# USB.net
KiCad netlist of a schematic drawn in EasyEDA Pro
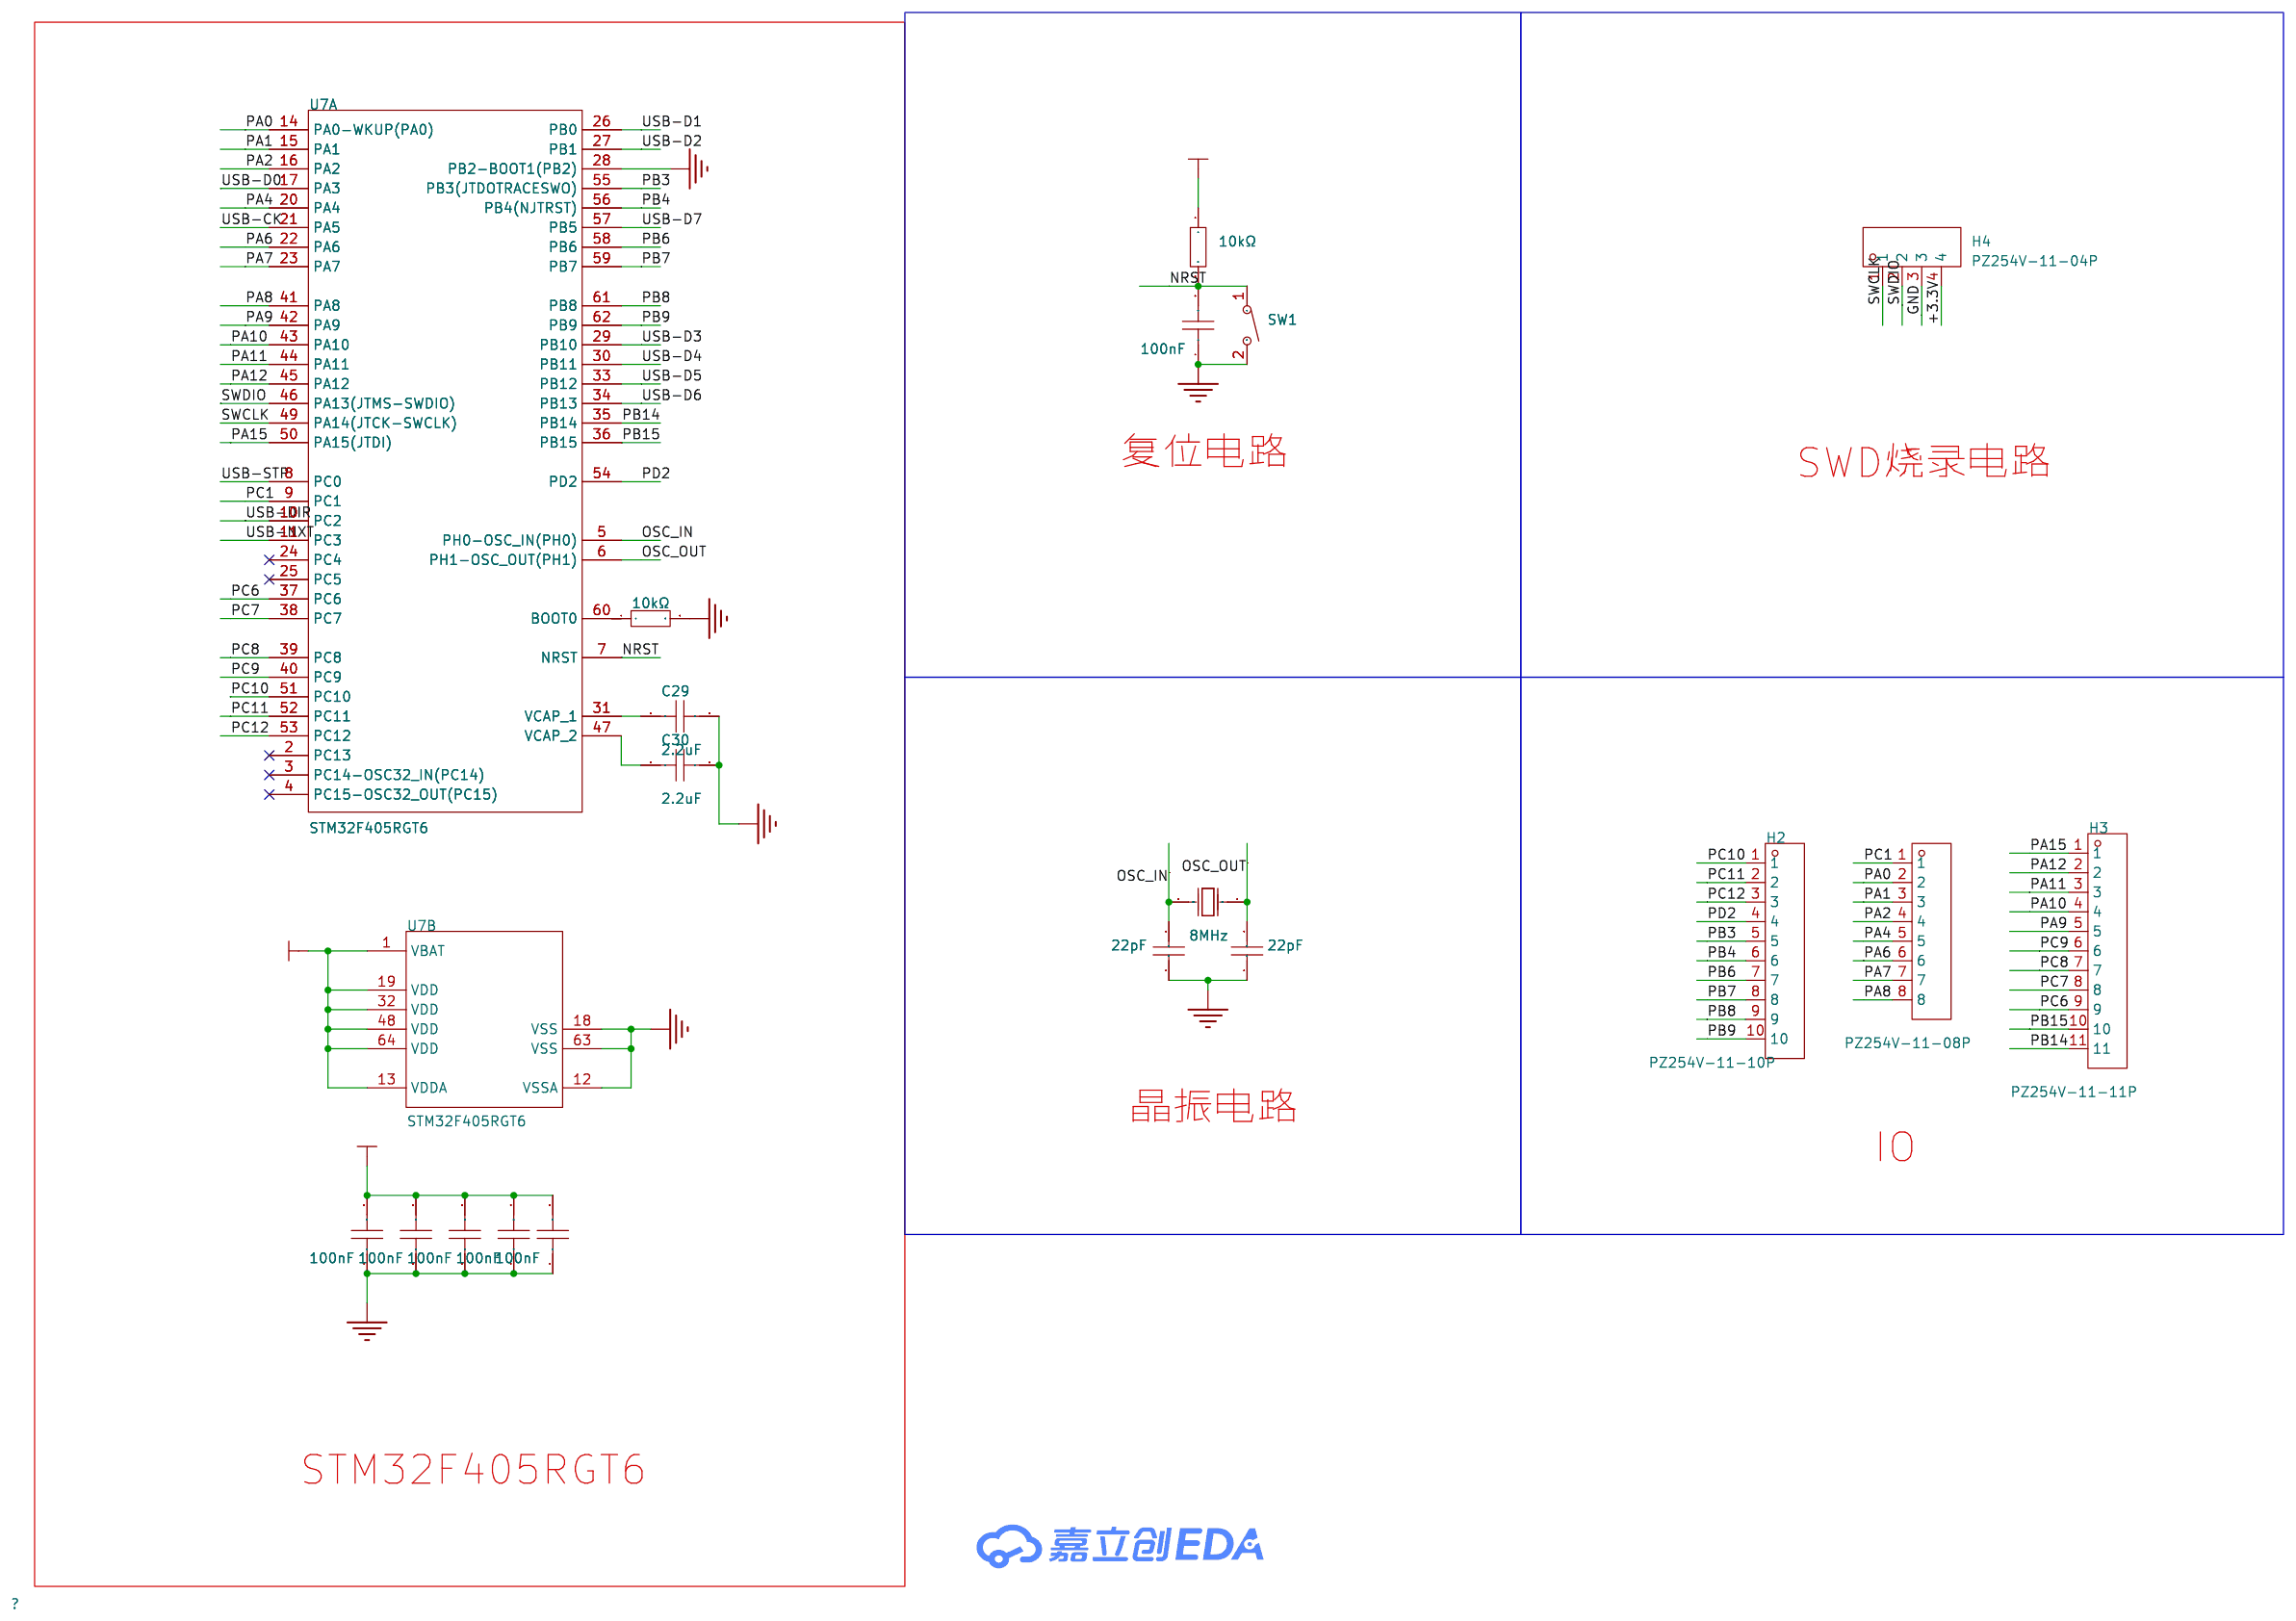
[diagram p0: P1]
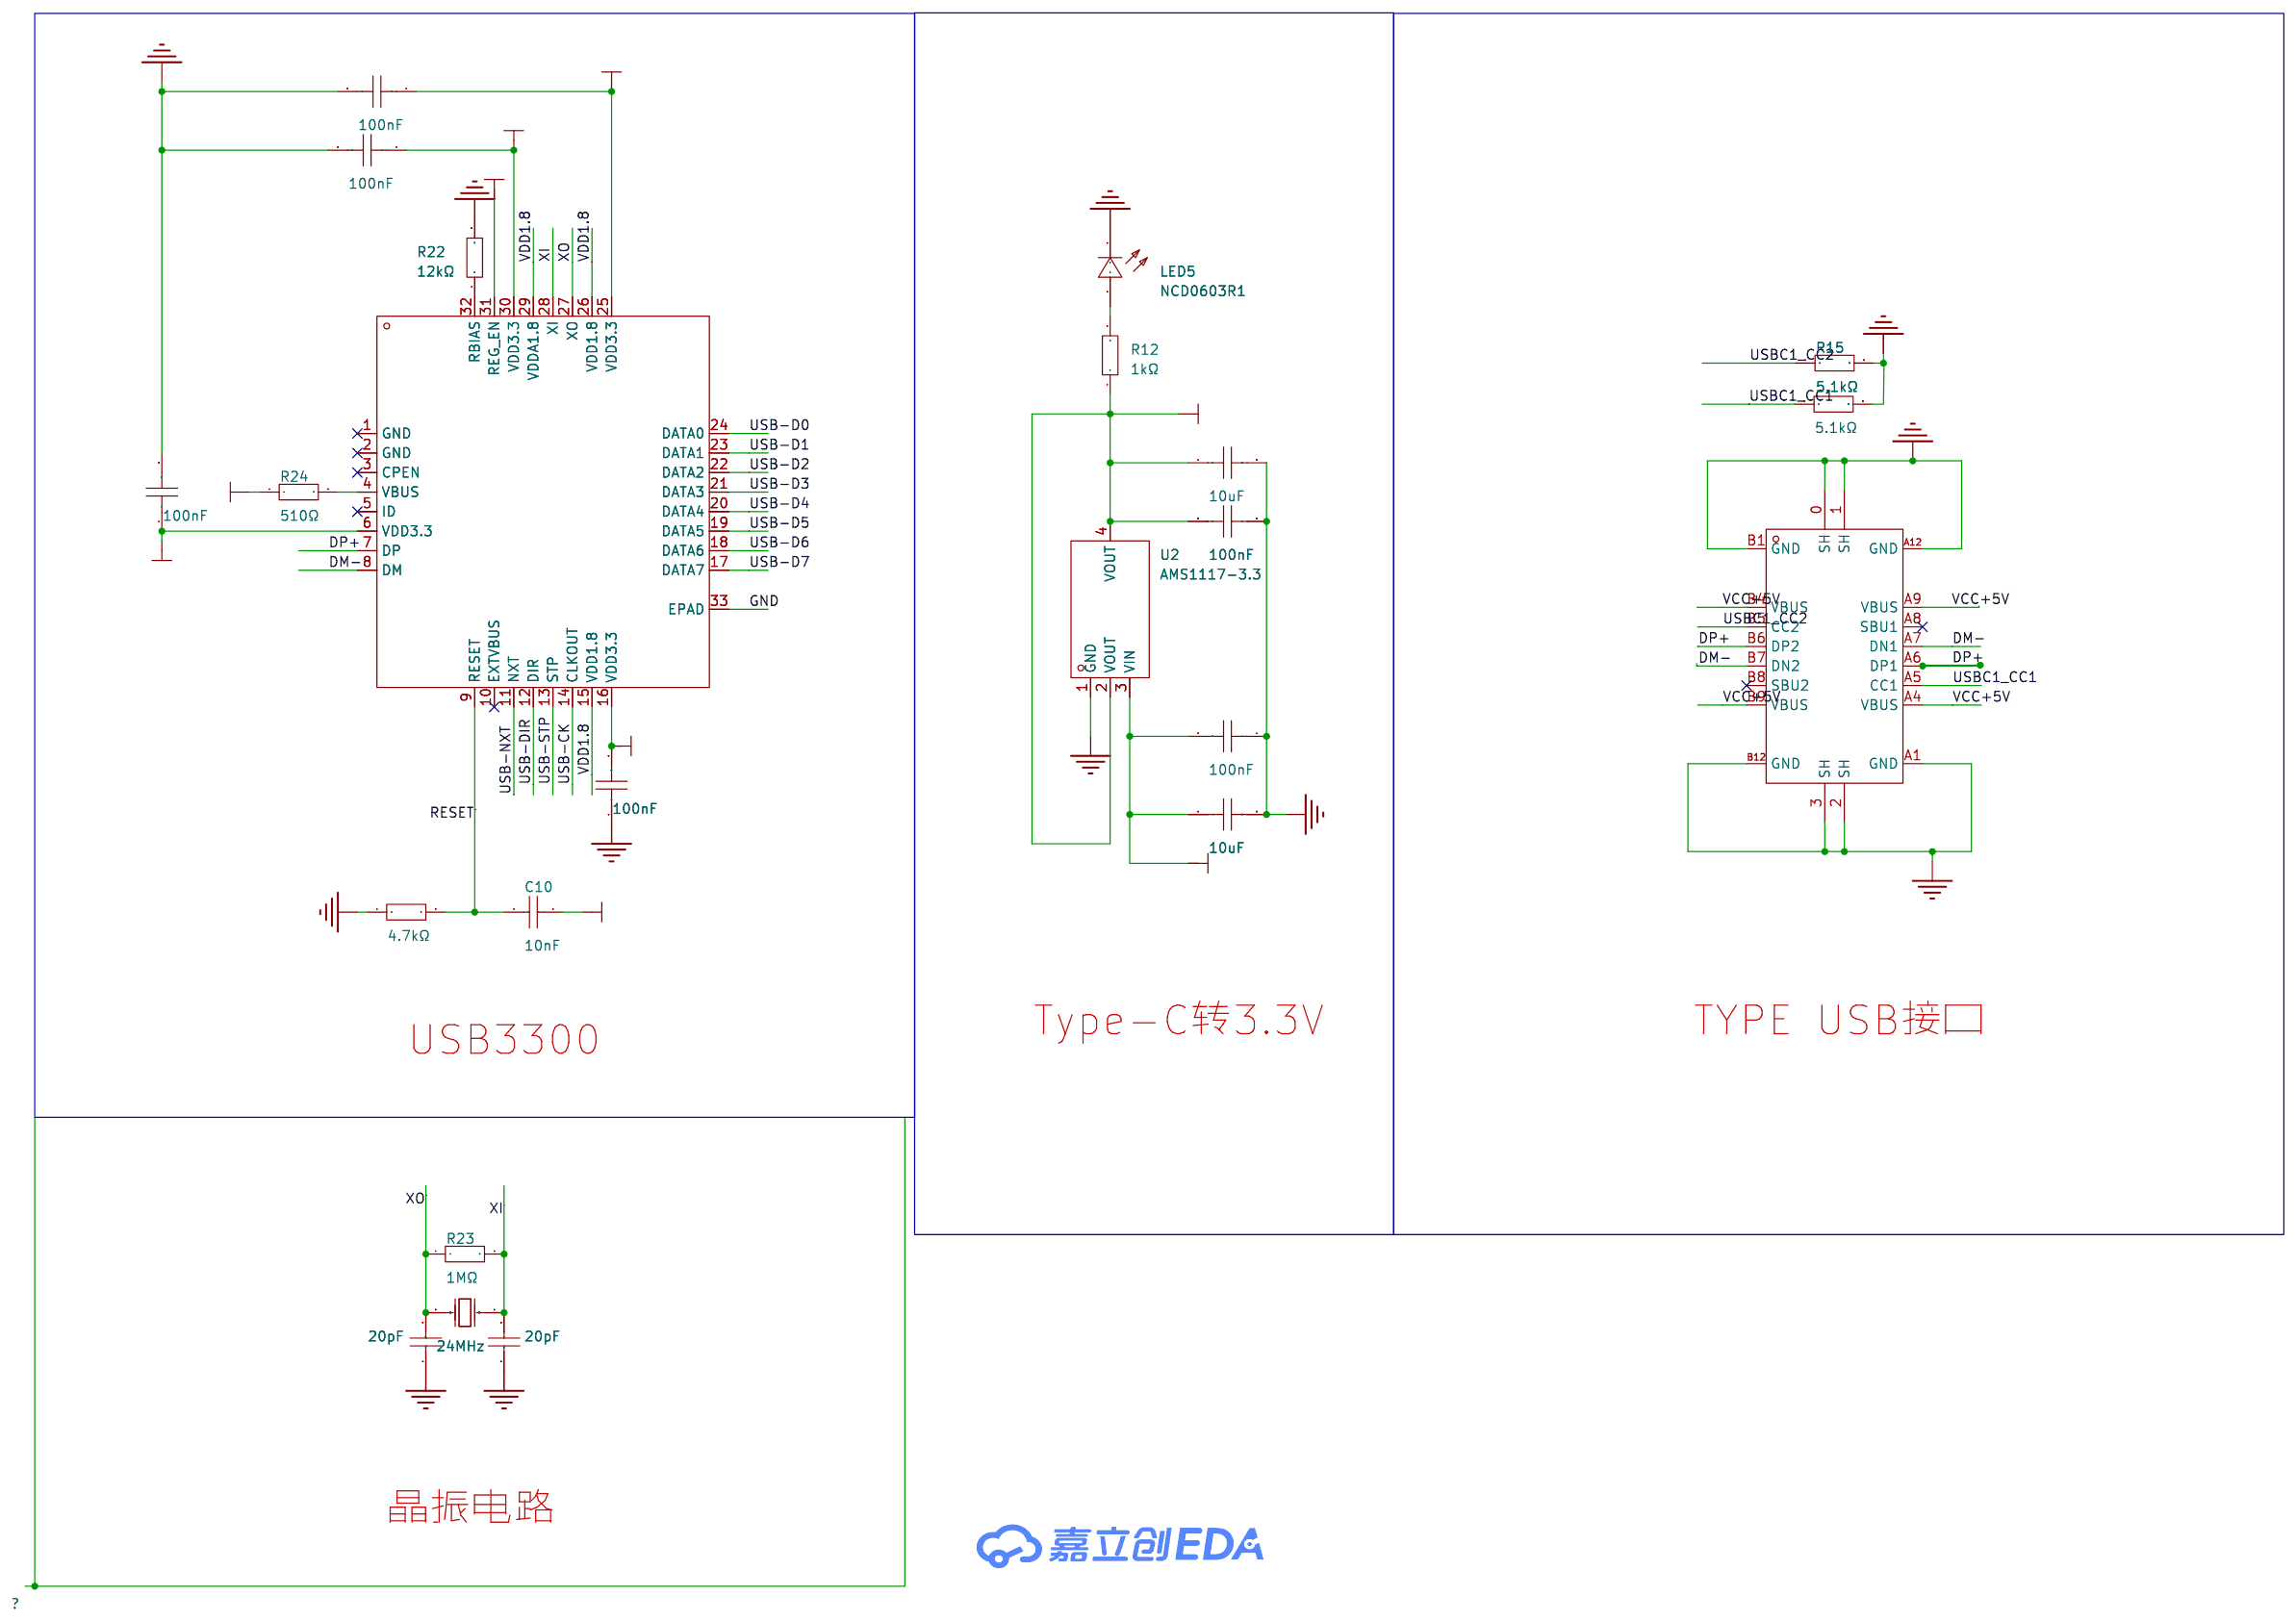
[diagram p1: P2]

(export (version "E")
  (design (tool "Eeschema 10.0.6"))
  (components
    (comp (ref "C20")
      (value "22pF")
      (footprint "easyedapro:C0603")
      (description "容值:22pF;精度:±5%;额定电压:50V;材质(温度系数):C0G;")
      (fields
        (field (name "Manufacturer Part") "CL10C220JB8NNNC")
        (field (name "Manufacturer") "SAMSUNG(三星)")
      )
      (libsource (lib "easyedapro") (part "CL10C220JB8NNNC"))
    )
    (comp (ref "C21")
      (value "22pF")
      (footprint "easyedapro:C0603")
      (description "容值:22pF;精度:±5%;额定电压:50V;材质(温度系数):C0G;")
      (fields
        (field (name "Manufacturer Part") "CL10C220JB8NNNC")
        (field (name "Manufacturer") "SAMSUNG(三星)")
      )
      (libsource (lib "easyedapro") (part "CL10C220JB8NNNC"))
    )
    (comp (ref "C22")
      (value "100nF")
      (footprint "easyedapro:C0603")
      (description "容值:100nF;精度:±10%;额定电压:50V;材质(温度系数):X7R;")
      (fields
        (field (name "Manufacturer Part") "CGA0603X7R104K500JT")
        (field (name "Manufacturer") "HRE(芯声)")
      )
      (libsource (lib "easyedapro") (part "CGA0603X7R104K500JT"))
    )
    (comp (ref "C29")
      (value "2.2uF")
      (footprint "easyedapro:C0603")
      (description "容值:2.2uF;精度:±10%;额定电压:50V;材质(温度系数):X5R;")
      (fields
        (field (name "Manufacturer Part") "CL10A225KB8NNNC")
        (field (name "Manufacturer") "SAMSUNG(三星)")
      )
      (libsource (lib "easyedapro") (part "CL10A225KB8NNNC"))
    )
    (comp (ref "C30")
      (value "2.2uF")
      (footprint "easyedapro:C0603")
      (description "容值:2.2uF;精度:±10%;额定电压:50V;材质(温度系数):X5R;")
      (fields
        (field (name "Manufacturer Part") "CL10A225KB8NNNC")
        (field (name "Manufacturer") "SAMSUNG(三星)")
      )
      (libsource (lib "easyedapro") (part "CL10A225KB8NNNC"))
    )
    (comp (ref "C35")
      (value "100nF")
      (footprint "easyedapro:C0603")
      (description "容值:100nF;精度:±10%;额定电压:50V;材质(温度系数):X7R;")
      (fields
        (field (name "Manufacturer Part") "CGA0603X7R104K500JT")
        (field (name "Manufacturer") "HRE(芯声)")
      )
      (libsource (lib "easyedapro") (part "CGA0603X7R104K500JT"))
    )
    (comp (ref "C36")
      (value "100nF")
      (footprint "easyedapro:C0603")
      (description "容值:100nF;精度:±10%;额定电压:50V;材质(温度系数):X7R;")
      (fields
        (field (name "Manufacturer Part") "CGA0603X7R104K500JT")
        (field (name "Manufacturer") "HRE(芯声)")
      )
      (libsource (lib "easyedapro") (part "CGA0603X7R104K500JT"))
    )
    (comp (ref "C37")
      (value "100nF")
      (footprint "easyedapro:C0603")
      (description "容值:100nF;精度:±10%;额定电压:50V;材质(温度系数):X7R;")
      (fields
        (field (name "Manufacturer Part") "CGA0603X7R104K500JT")
        (field (name "Manufacturer") "HRE(芯声)")
      )
      (libsource (lib "easyedapro") (part "CGA0603X7R104K500JT"))
    )
    (comp (ref "C38")
      (value "100nF")
      (footprint "easyedapro:C0603")
      (description "容值:100nF;精度:±10%;额定电压:50V;材质(温度系数):X7R;")
      (fields
        (field (name "Manufacturer Part") "CGA0603X7R104K500JT")
        (field (name "Manufacturer") "HRE(芯声)")
      )
      (libsource (lib "easyedapro") (part "CGA0603X7R104K500JT"))
    )
    (comp (ref "C39")
      (value "100nF")
      (footprint "easyedapro:C0603")
      (description "容值:100nF;精度:±10%;额定电压:50V;材质(温度系数):X7R;")
      (fields
        (field (name "Manufacturer Part") "CGA0603X7R104K500JT")
        (field (name "Manufacturer") "HRE(芯声)")
      )
      (libsource (lib "easyedapro") (part "CGA0603X7R104K500JT"))
    )
    (comp (ref "H1")
      (value "PZ254V-11-08P")
      (footprint "easyedapro:HDR-TH_8P-P2.54-V-M")
      (fields (field (name "Manufacturer") "XFCN(兴飞)"))
      (libsource (lib "easyedapro") (part "PZ254V-11-08P"))
    )
    (comp (ref "H2")
      (value "PZ254V-11-10P")
      (footprint "easyedapro:HDR-TH_10P-P2.54-V-M")
      (fields (field (name "Manufacturer") "XFCN(兴飞)"))
      (libsource (lib "easyedapro") (part "PZ254V-11-10P"))
    )
    (comp (ref "H3")
      (value "PZ254V-11-11P")
      (footprint "easyedapro:HDR-TH_11P-P2.54-V-M")
      (fields (field (name "Manufacturer") "XFCN(兴飞)"))
      (libsource (lib "easyedapro") (part "PZ254V-11-11P"))
    )
    (comp (ref "H4")
      (value "PZ254V-11-04P")
      (footprint "easyedapro:HDR-TH_4P-P2.54-V-M")
      (fields (field (name "Manufacturer") "XFCN(兴飞)"))
      (libsource (lib "easyedapro") (part "PZ254V-11-04P_C2691448"))
    )
    (comp (ref "R18")
      (value "10kΩ")
      (footprint "easyedapro:R0603")
      (description "电阻类型:厚膜电阻;阻值:10kΩ;精度:±1%;功率:100mW;最大工作电压:75V;温度系数:±100ppm/°C;")
      (fields
        (field (name "Manufacturer Part") "0603WAF1002T5E")
        (field (name "Manufacturer") "UNI-ROYAL(厚声)")
      )
      (libsource (lib "easyedapro") (part "0603WAF1002T5E"))
    )
    (comp (ref "R19")
      (value "10kΩ")
      (footprint "easyedapro:R0603")
      (description "电阻类型:厚膜电阻;阻值:10kΩ;精度:±1%;功率:100mW;最大工作电压:75V;温度系数:±100ppm/°C;")
      (fields
        (field (name "Manufacturer Part") "0603WAF1002T5E")
        (field (name "Manufacturer") "UNI-ROYAL(厚声)")
      )
      (libsource (lib "easyedapro") (part "0603WAF1002T5E"))
    )
    (comp (ref "SW1")
      (value "TS-1092S-B3D2-G")
      (footprint "easyedapro:SW-SMD_L6.1-W3.6-LS7.9")
      (description "电路结构:单刀单掷;按钮形状:矩形按钮;作用力:250gf;安装方式:立贴;开关长度:6.1mm;开关宽度:3.6mm;开关高度:2.5mm;带支架:不带;机械寿命:-;")
      (fields (field (name "Manufacturer") "Yuandi(元迪)"))
      (libsource (lib "easyedapro") (part "TS-1092S-B3D2-G"))
    )
    (comp (ref "U7")
      (value "STM32F405RGT6")
      (footprint "easyedapro:LQFP-64_L10.0-W10.0-P0.50-LS12.0-BL")
      (description "CPU内核:ARM-M4;CPU最大主频:168MHz;应用领域:-;")
      (fields (field (name "Manufacturer") "ST(意法半导体)"))
      (libsource (lib "easyedapro") (part "STM32F405RGT6"))
    )
    (comp (ref "X3")
      (value "8MHz")
      (footprint "easyedapro:OSC-SMD_L5.0-W3.2")
      (description "晶振类型:贴片晶振;频率:8MHz;常温频差:±30ppm;外接负载电容:20pF;频率稳定度(全温):±20ppm;")
      (fields (field (name "Manufacturer Part") "TAXM8M2QLFCDT1T") (field (name "Manufacturer") "YJX(雅晶鑫)"))
      (libsource (lib "easyedapro") (part "SMD-5032_2P 8M 20pf 30ppm"))
    )
    (comp (ref "C10")
      (value "10nF")
      (footprint "easyedapro:C0603")
      (description "容值:10nF;精度:±10%;额定电压:50V;材质(温度系数):X7R;")
      (fields
        (field (name "Manufacturer Part") "CC0603KRX7R9BB103")
        (field (name "Manufacturer") "YAGEO(国巨)")
      )
      (libsource (lib "easyedapro") (part "CC0603KRX7R9BB103"))
    )
    (comp (ref "C11")
      (value "10uF")
      (footprint "easyedapro:C0603")
      (description "容值:10uF;精度:±10%;额定电压:10V;材质(温度系数):X5R;")
      (fields
        (field (name "Manufacturer Part") "CGA0603X5R106K100JT")
        (field (name "Manufacturer") "HRE(芯声)")
      )
      (libsource (lib "easyedapro") (part "CGA0603X5R106K100JT"))
    )
    (comp (ref "C12")
      (value "100nF")
      (footprint "easyedapro:C0603")
      (description "容值:100nF;精度:±10%;额定电压:50V;材质(温度系数):X7R;")
      (fields
        (field (name "Manufacturer Part") "CGA0603X7R104K500JT")
        (field (name "Manufacturer") "HRE(芯声)")
      )
      (libsource (lib "easyedapro") (part "CGA0603X7R104K500JT"))
    )
    (comp (ref "C13")
      (value "100nF")
      (footprint "easyedapro:C0603")
      (description "容值:100nF;精度:±10%;额定电压:50V;材质(温度系数):X7R;")
      (fields
        (field (name "Manufacturer Part") "CGA0603X7R104K500JT")
        (field (name "Manufacturer") "HRE(芯声)")
      )
      (libsource (lib "easyedapro") (part "CGA0603X7R104K500JT"))
    )
    (comp (ref "C14")
      (value "10uF")
      (footprint "easyedapro:C0603")
      (description "容值:10uF;精度:±10%;额定电压:10V;材质(温度系数):X5R;")
      (fields
        (field (name "Manufacturer Part") "CGA0603X5R106K100JT")
        (field (name "Manufacturer") "HRE(芯声)")
      )
      (libsource (lib "easyedapro") (part "CGA0603X5R106K100JT"))
    )
    (comp (ref "C23")
      (value "20pF")
      (footprint "easyedapro:C0603")
      (description "容值:20pF;精度:±5%;额定电压:50V;材质(温度系数):C0G;")
      (fields
        (field (name "Manufacturer Part") "CL10C200JB8NNNC")
        (field (name "Manufacturer") "SAMSUNG(三星)")
      )
      (libsource (lib "easyedapro") (part "CL10C200JB8NNNC"))
    )
    (comp (ref "C24")
      (value "20pF")
      (footprint "easyedapro:C0603")
      (description "容值:20pF;精度:±5%;额定电压:50V;材质(温度系数):C0G;")
      (fields
        (field (name "Manufacturer Part") "CL10C200JB8NNNC")
        (field (name "Manufacturer") "SAMSUNG(三星)")
      )
      (libsource (lib "easyedapro") (part "CL10C200JB8NNNC"))
    )
    (comp (ref "C31")
      (value "100nF")
      (footprint "easyedapro:C0603")
      (description "容值:100nF;精度:±10%;额定电压:50V;材质(温度系数):X7R;")
      (fields
        (field (name "Manufacturer Part") "CGA0603X7R104K500JT")
        (field (name "Manufacturer") "HRE(芯声)")
      )
      (libsource (lib "easyedapro") (part "CGA0603X7R104K500JT"))
    )
    (comp (ref "C32")
      (value "100nF")
      (footprint "easyedapro:C0603")
      (description "容值:100nF;精度:±10%;额定电压:50V;材质(温度系数):X7R;")
      (fields
        (field (name "Manufacturer Part") "CGA0603X7R104K500JT")
        (field (name "Manufacturer") "HRE(芯声)")
      )
      (libsource (lib "easyedapro") (part "CGA0603X7R104K500JT"))
    )
    (comp (ref "C33")
      (value "100nF")
      (footprint "easyedapro:C0603")
      (description "容值:100nF;精度:±10%;额定电压:50V;材质(温度系数):X7R;")
      (fields
        (field (name "Manufacturer Part") "CGA0603X7R104K500JT")
        (field (name "Manufacturer") "HRE(芯声)")
      )
      (libsource (lib "easyedapro") (part "CGA0603X7R104K500JT"))
    )
    (comp (ref "C34")
      (value "100nF")
      (footprint "easyedapro:C0603")
      (description "容值:100nF;精度:±10%;额定电压:50V;材质(温度系数):X7R;")
      (fields
        (field (name "Manufacturer Part") "CGA0603X7R104K500JT")
        (field (name "Manufacturer") "HRE(芯声)")
      )
      (libsource (lib "easyedapro") (part "CGA0603X7R104K500JT"))
    )
    (comp (ref "LED5")
      (value "NCD0603R1")
      (footprint "easyedapro:LED0603-RD_RED")
      (fields (field (name "Manufacturer") "国星光电"))
      (libsource (lib "easyedapro") (part "FC-DA1608HRK-620D"))
    )
    (comp (ref "R11")
      (value "4.7kΩ")
      (footprint "easyedapro:R0603")
      (description "电阻类型:厚膜电阻;阻值:4.7kΩ;精度:±1%;功率:100mW;最大工作电压:75V;温度系数:±100ppm/°C;")
      (fields
        (field (name "Manufacturer Part") "0603WAF4701T5E")
        (field (name "Manufacturer") "UNI-ROYAL(厚声)")
      )
      (libsource (lib "easyedapro") (part "0603WAF4701T5E"))
    )
    (comp (ref "R12")
      (value "1kΩ")
      (footprint "easyedapro:R0603")
      (description "电阻类型:厚膜电阻;阻值:1kΩ;精度:±1%;功率:100mW;最大工作电压:75V;温度系数:±100ppm/°C;")
      (fields
        (field (name "Manufacturer Part") "0603WAF1001T5E")
        (field (name "Manufacturer") "UNI-ROYAL(厚声)")
      )
      (libsource (lib "easyedapro") (part "0603WAF1001T5E"))
    )
    (comp (ref "R14")
      (value "5.1kΩ")
      (footprint "easyedapro:R0603")
      (description "电阻类型:厚膜电阻;阻值:5.1kΩ;精度:±1%;功率:100mW;最大工作电压:75V;温度系数:±100ppm/°C;")
      (fields
        (field (name "Manufacturer Part") "0603WAF5101T5E")
        (field (name "Manufacturer") "UNI-ROYAL(厚声)")
      )
      (libsource (lib "easyedapro") (part "0603WAF5101T5E"))
    )
    (comp (ref "R15")
      (value "5.1kΩ")
      (footprint "easyedapro:R0603")
      (description "电阻类型:厚膜电阻;阻值:5.1kΩ;精度:±1%;功率:100mW;最大工作电压:75V;温度系数:±100ppm/°C;")
      (fields
        (field (name "Manufacturer Part") "0603WAF5101T5E")
        (field (name "Manufacturer") "UNI-ROYAL(厚声)")
      )
      (libsource (lib "easyedapro") (part "0603WAF5101T5E"))
    )
    (comp (ref "R22")
      (value "12kΩ")
      (footprint "easyedapro:R0603")
      (description "电阻类型:厚膜电阻;阻值:12kΩ;精度:±1%;功率:100mW;最大工作电压:75V;温度系数:±100ppm/°C;")
      (fields
        (field (name "Manufacturer Part") "0603WAF1202T5E")
        (field (name "Manufacturer") "UNI-ROYAL(厚声)")
      )
      (libsource (lib "easyedapro") (part "0603WAF1202T5E"))
    )
    (comp (ref "R23")
      (value "1MΩ")
      (footprint "easyedapro:R0603")
      (description "电阻类型:厚膜电阻;阻值:1MΩ;精度:±1%;功率:100mW;最大工作电压:75V;温度系数:±100ppm/°C;")
      (fields
        (field (name "Manufacturer Part") "0603WAF1004T5E")
        (field (name "Manufacturer") "UNI-ROYAL(厚声)")
      )
      (libsource (lib "easyedapro") (part "0603WAF1004T5E"))
    )
    (comp (ref "R24")
      (value "510Ω")
      (footprint "easyedapro:R0603")
      (description "电阻类型:厚膜电阻;阻值:510Ω;精度:±1%;功率:100mW;最大工作电压:75V;温度系数:±100ppm/°C;")
      (fields
        (field (name "Manufacturer Part") "0603WAF5100T5E")
        (field (name "Manufacturer") "UNI-ROYAL(厚声)")
      )
      (libsource (lib "easyedapro") (part "0603WAF5100T5E"))
    )
    (comp (ref "U2")
      (value "AMS1117-3.3")
      (footprint "easyedapro:SOT-223-3_L6.5-W3.4-P2.30-LS7.0-BR")
      (description "输出类型:固定;最大输入电压:-;输出电压:3.3V;最大输出电流:1A;电源纹波抑制比(PSRR):72dB@(120Hz);输出极性:正极;")
      (fields (field (name "Manufacturer") "AMS"))
      (libsource (lib "easyedapro") (part "AMS1117-3.3"))
    )
    (comp (ref "USB3301")
      (value "USB3300-EZK-TR")
      (footprint "easyedapro:QFN-32_L5.0-W5.0-P0.50-BL-EP3.4")
      (description "应用功能:控制器;接口协议:-;")
      (fields (field (name "Manufacturer") "MICROCHIP(美国微芯)"))
      (libsource (lib "easyedapro") (part "USB3300-EZK-TR"))
    )
    (comp (ref "USBC2")
      (value "TYPE-C-31-M-12")
      (footprint "easyedapro:USB-C_SMD-TYPE-C-31-M-12")
      (description "连接器类型:Type-C;标准:-;公母:母;安装方式:-;触点数量:16P;端口数量:1;额定电流 - 电源:5A;工作温度范围:-;")
      (fields (field (name "Manufacturer") "韩国韩荣"))
      (libsource (lib "easyedapro") (part "TYPE-C-31-M-12"))
    )
    (comp (ref "X4")
      (value "24MHz")
      (footprint "easyedapro:HC-49US_L11.5-W4.5-P4.88")
      (description "晶振类型:直插晶振;频率:24MHz;常温频差:±20ppm;外接负载电容:20pF;频率稳定度(全温):±30ppm;")
      (fields (field (name "Manufacturer Part") "X49SD24MSD2SC") (field (name "Manufacturer") "YXC(扬兴晶振)"))
      (libsource (lib "easyedapro") (part "X49SD24MSD2SC"))
    )
  )
  (nets
    (net (code "1") (name "+3.3V") (class "Default")
      (node (ref "C10") (pin "2") (pinfunction "2_2") (pintype "input"))
      (node (ref "C13") (pin "2") (pinfunction "2_2") (pintype "unspecified"))
      (node (ref "C14") (pin "1") (pinfunction "1_1") (pintype "unspecified"))
      (node (ref "C31") (pin "2") (pinfunction "2_2") (pintype "unspecified"))
      (node (ref "C32") (pin "1") (pinfunction "1_1") (pintype "unspecified"))
      (node (ref "C33") (pin "1") (pinfunction "1_1") (pintype "unspecified"))
      (node (ref "C34") (pin "1") (pinfunction "1_1") (pintype "unspecified"))
      (node (ref "C35") (pin "2") (pinfunction "2_2") (pintype "unspecified"))
      (node (ref "C36") (pin "2") (pinfunction "2_2") (pintype "unspecified"))
      (node (ref "C37") (pin "2") (pinfunction "2_2") (pintype "unspecified"))
      (node (ref "C38") (pin "2") (pinfunction "2_2") (pintype "unspecified"))
      (node (ref "C39") (pin "2") (pinfunction "2_2") (pintype "unspecified"))
      (node (ref "H4") (pin "4") (pinfunction "4_4") (pintype "unspecified"))
      (node (ref "R12") (pin "1") (pinfunction "1_1") (pintype "input"))
      (node (ref "R19") (pin "1") (pinfunction "1_1") (pintype "input"))
      (node (ref "U2") (pin "2") (pinfunction "VOUT_2") (pintype "unspecified"))
      (node (ref "U2") (pin "4") (pinfunction "VOUT_4") (pintype "unspecified"))
      (node (ref "U7") (pin "1") (pinfunction "VBAT_1") (pintype "unspecified"))
      (node (ref "U7") (pin "13") (pinfunction "VDDA_13") (pintype "unspecified"))
      (node (ref "U7") (pin "19") (pinfunction "VDD_19") (pintype "unspecified"))
      (node (ref "U7") (pin "32") (pinfunction "VDD_32") (pintype "unspecified"))
      (node (ref "U7") (pin "48") (pinfunction "VDD_48") (pintype "unspecified"))
      (node (ref "U7") (pin "64") (pinfunction "VDD_64") (pintype "unspecified"))
      (node (ref "USB3301") (pin "16") (pinfunction "VDD3.3_16") (pintype "unspecified"))
      (node (ref "USB3301") (pin "25") (pinfunction "VDD3.3_25") (pintype "unspecified"))
      (node (ref "USB3301") (pin "30") (pinfunction "VDD3.3_30") (pintype "unspecified"))
      (node (ref "USB3301") (pin "31") (pinfunction "REG_EN_31") (pintype "unspecified"))
      (node (ref "USB3301") (pin "6") (pinfunction "VDD3.3_6") (pintype "unspecified"))
    )
    (net (code "2") (name "DM-") (class "Default")
      (node (ref "USB3301") (pin "8") (pinfunction "DM_8") (pintype "unspecified"))
      (node (ref "USBC2") (pin "A7") (pinfunction "DN1_A7") (pintype "unspecified"))
      (node (ref "USBC2") (pin "B7") (pinfunction "DN2_B7") (pintype "unspecified"))
    )
    (net (code "3") (name "DP+") (class "Default")
      (node (ref "USB3301") (pin "7") (pinfunction "DP_7") (pintype "unspecified"))
      (node (ref "USBC2") (pin "A6") (pinfunction "DP1_A6") (pintype "unspecified"))
      (node (ref "USBC2") (pin "B6") (pinfunction "DP2_B6") (pintype "unspecified"))
    )
    (net (code "4") (name "GND") (class "Default")
      (node (ref "C11") (pin "2") (pinfunction "2_2") (pintype "unspecified"))
      (node (ref "C12") (pin "1") (pinfunction "1_1") (pintype "unspecified"))
      (node (ref "C13") (pin "1") (pinfunction "1_1") (pintype "unspecified"))
      (node (ref "C14") (pin "2") (pinfunction "2_2") (pintype "unspecified"))
      (node (ref "C20") (pin "1") (pinfunction "1_1") (pintype "input"))
      (node (ref "C21") (pin "1") (pinfunction "1_1") (pintype "input"))
      (node (ref "C22") (pin "1") (pinfunction "1_1") (pintype "unspecified"))
      (node (ref "C23") (pin "1") (pinfunction "1_1") (pintype "input"))
      (node (ref "C24") (pin "1") (pinfunction "1_1") (pintype "input"))
      (node (ref "C29") (pin "2") (pinfunction "2_2") (pintype "unspecified"))
      (node (ref "C30") (pin "2") (pinfunction "2_2") (pintype "unspecified"))
      (node (ref "C31") (pin "1") (pinfunction "1_1") (pintype "unspecified"))
      (node (ref "C32") (pin "2") (pinfunction "2_2") (pintype "unspecified"))
      (node (ref "C33") (pin "2") (pinfunction "2_2") (pintype "unspecified"))
      (node (ref "C34") (pin "2") (pinfunction "2_2") (pintype "unspecified"))
      (node (ref "C35") (pin "1") (pinfunction "1_1") (pintype "unspecified"))
      (node (ref "C36") (pin "1") (pinfunction "1_1") (pintype "unspecified"))
      (node (ref "C37") (pin "1") (pinfunction "1_1") (pintype "unspecified"))
      (node (ref "C38") (pin "1") (pinfunction "1_1") (pintype "unspecified"))
      (node (ref "C39") (pin "1") (pinfunction "1_1") (pintype "unspecified"))
      (node (ref "H4") (pin "3") (pinfunction "3_3") (pintype "unspecified"))
      (node (ref "LED5") (pin "1") (pinfunction "K_1") (pintype "input"))
      (node (ref "R11") (pin "1") (pinfunction "1_1") (pintype "input"))
      (node (ref "R15") (pin "2") (pinfunction "2_2") (pintype "input"))
      (node (ref "R18") (pin "2") (pinfunction "2_2") (pintype "input"))
      (node (ref "R22") (pin "2") (pinfunction "2_2") (pintype "input"))
      (node (ref "SW1") (pin "2") (pinfunction "2_2") (pintype "unspecified"))
      (node (ref "U2") (pin "1") (pinfunction "GND_1") (pintype "unspecified"))
      (node (ref "U7") (pin "12") (pinfunction "VSSA_12") (pintype "unspecified"))
      (node (ref "U7") (pin "18") (pinfunction "VSS_18") (pintype "unspecified"))
      (node (ref "U7") (pin "28") (pinfunction "PB2-BOOT1(PB2)_28") (pintype "bidirectional"))
      (node (ref "U7") (pin "63") (pinfunction "VSS_63") (pintype "unspecified"))
      (node (ref "USB3301") (pin "33") (pinfunction "EPAD_33") (pintype "unspecified"))
      (node (ref "USBC2") (pin "0") (pinfunction "SH_0") (pintype "unspecified"))
      (node (ref "USBC2") (pin "1") (pinfunction "SH_1") (pintype "unspecified"))
      (node (ref "USBC2") (pin "2") (pinfunction "SH_2") (pintype "unspecified"))
      (node (ref "USBC2") (pin "3") (pinfunction "SH_3") (pintype "unspecified"))
      (node (ref "USBC2") (pin "A1") (pinfunction "GND_A1") (pintype "unspecified"))
      (node (ref "USBC2") (pin "A12") (pinfunction "GND_A12") (pintype "unspecified"))
      (node (ref "USBC2") (pin "B1") (pinfunction "GND_B1") (pintype "unspecified"))
      (node (ref "USBC2") (pin "B12") (pinfunction "GND_B12") (pintype "unspecified"))
    )
    (net (code "5") (name "NRST") (class "Default")
      (node (ref "C22") (pin "2") (pinfunction "2_2") (pintype "unspecified"))
      (node (ref "R19") (pin "2") (pinfunction "2_2") (pintype "input"))
      (node (ref "SW1") (pin "1") (pinfunction "1_1") (pintype "unspecified"))
      (node (ref "U7") (pin "7") (pinfunction "NRST_7") (pintype "bidirectional"))
    )
    (net (code "6") (name "Net-(LED5-A)") (class "Default")
      (node (ref "LED5") (pin "2") (pinfunction "A_2") (pintype "input"))
      (node (ref "R12") (pin "2") (pinfunction "2_2") (pintype "input"))
    )
    (net (code "7") (name "Net-(U7A-BOOT0)") (class "Default")
      (node (ref "R18") (pin "1") (pinfunction "1_1") (pintype "input"))
      (node (ref "U7") (pin "60") (pinfunction "BOOT0_60") (pintype "unspecified"))
    )
    (net (code "8") (name "Net-(U7A-VCAP_1)") (class "Default")
      (node (ref "C29") (pin "1") (pinfunction "1_1") (pintype "unspecified"))
      (node (ref "U7") (pin "31") (pinfunction "VCAP_1_31") (pintype "unspecified"))
    )
    (net (code "9") (name "Net-(U7A-VCAP_2)") (class "Default")
      (node (ref "C30") (pin "1") (pinfunction "1_1") (pintype "unspecified"))
      (node (ref "U7") (pin "47") (pinfunction "VCAP_2_47") (pintype "unspecified"))
    )
    (net (code "10") (name "Net-(USB3301-RBIAS)") (class "Default")
      (node (ref "R22") (pin "1") (pinfunction "1_1") (pintype "input"))
      (node (ref "USB3301") (pin "32") (pinfunction "RBIAS_32") (pintype "unspecified"))
    )
    (net (code "11") (name "Net-(USB3301-VBUS)") (class "Default")
      (node (ref "R24") (pin "2") (pinfunction "2_2") (pintype "input"))
      (node (ref "USB3301") (pin "4") (pinfunction "VBUS_4") (pintype "unspecified"))
    )
    (net (code "12") (name "OSC_IN") (class "Default")
      (node (ref "C20") (pin "2") (pinfunction "2_2") (pintype "input"))
      (node (ref "U7") (pin "5") (pinfunction "PH0-OSC_IN(PH0)_5") (pintype "bidirectional"))
      (node (ref "X3") (pin "2") (pinfunction "OSC2_2") (pintype "input"))
    )
    (net (code "13") (name "OSC_OUT") (class "Default")
      (node (ref "C21") (pin "2") (pinfunction "2_2") (pintype "input"))
      (node (ref "U7") (pin "6") (pinfunction "PH1-OSC_OUT(PH1)_6") (pintype "bidirectional"))
      (node (ref "X3") (pin "1") (pinfunction "OSC1_1") (pintype "input"))
    )
    (net (code "14") (name "PA0") (class "Default")
      (node (ref "H1") (pin "2") (pinfunction "2_2") (pintype "unspecified"))
      (node (ref "U7") (pin "14") (pinfunction "PA0-WKUP(PA0)_14") (pintype "bidirectional"))
    )
    (net (code "15") (name "PA1") (class "Default")
      (node (ref "H1") (pin "3") (pinfunction "3_3") (pintype "unspecified"))
      (node (ref "U7") (pin "15") (pinfunction "PA1_15") (pintype "bidirectional"))
    )
    (net (code "16") (name "PA2") (class "Default")
      (node (ref "H1") (pin "4") (pinfunction "4_4") (pintype "unspecified"))
      (node (ref "U7") (pin "16") (pinfunction "PA2_16") (pintype "bidirectional"))
    )
    (net (code "17") (name "PA4") (class "Default")
      (node (ref "H1") (pin "5") (pinfunction "5_5") (pintype "unspecified"))
      (node (ref "U7") (pin "20") (pinfunction "PA4_20") (pintype "bidirectional"))
    )
    (net (code "18") (name "PA6") (class "Default")
      (node (ref "H1") (pin "6") (pinfunction "6_6") (pintype "unspecified"))
      (node (ref "U7") (pin "22") (pinfunction "PA6_22") (pintype "bidirectional"))
    )
    (net (code "19") (name "PA7") (class "Default")
      (node (ref "H1") (pin "7") (pinfunction "7_7") (pintype "unspecified"))
      (node (ref "U7") (pin "23") (pinfunction "PA7_23") (pintype "bidirectional"))
    )
    (net (code "20") (name "PA8") (class "Default")
      (node (ref "H1") (pin "8") (pinfunction "8_8") (pintype "unspecified"))
      (node (ref "U7") (pin "41") (pinfunction "PA8_41") (pintype "bidirectional"))
    )
    (net (code "21") (name "PA9") (class "Default")
      (node (ref "H3") (pin "5") (pinfunction "5_5") (pintype "unspecified"))
      (node (ref "U7") (pin "42") (pinfunction "PA9_42") (pintype "bidirectional"))
    )
    (net (code "22") (name "PA10") (class "Default")
      (node (ref "H3") (pin "4") (pinfunction "4_4") (pintype "unspecified"))
      (node (ref "U7") (pin "43") (pinfunction "PA10_43") (pintype "bidirectional"))
    )
    (net (code "23") (name "PA11") (class "Default")
      (node (ref "H3") (pin "3") (pinfunction "3_3") (pintype "unspecified"))
      (node (ref "U7") (pin "44") (pinfunction "PA11_44") (pintype "bidirectional"))
    )
    (net (code "24") (name "PA12") (class "Default")
      (node (ref "H3") (pin "2") (pinfunction "2_2") (pintype "unspecified"))
      (node (ref "U7") (pin "45") (pinfunction "PA12_45") (pintype "bidirectional"))
    )
    (net (code "25") (name "PA15") (class "Default")
      (node (ref "H3") (pin "1") (pinfunction "1_1") (pintype "unspecified"))
      (node (ref "U7") (pin "50") (pinfunction "PA15(JTDI)_50") (pintype "bidirectional"))
    )
    (net (code "26") (name "PB3") (class "Default")
      (node (ref "H2") (pin "5") (pinfunction "5_5") (pintype "unspecified"))
      (node (ref "U7") (pin "55") (pinfunction "PB3(JTDOTRACESWO)_55") (pintype "bidirectional"))
    )
    (net (code "27") (name "PB4") (class "Default")
      (node (ref "H2") (pin "6") (pinfunction "6_6") (pintype "unspecified"))
      (node (ref "U7") (pin "56") (pinfunction "PB4(NJTRST)_56") (pintype "bidirectional"))
    )
    (net (code "28") (name "PB6") (class "Default")
      (node (ref "H2") (pin "7") (pinfunction "7_7") (pintype "unspecified"))
      (node (ref "U7") (pin "58") (pinfunction "PB6_58") (pintype "bidirectional"))
    )
    (net (code "29") (name "PB7") (class "Default")
      (node (ref "H2") (pin "8") (pinfunction "8_8") (pintype "unspecified"))
      (node (ref "U7") (pin "59") (pinfunction "PB7_59") (pintype "bidirectional"))
    )
    (net (code "30") (name "PB8") (class "Default")
      (node (ref "H2") (pin "9") (pinfunction "9_9") (pintype "unspecified"))
      (node (ref "U7") (pin "61") (pinfunction "PB8_61") (pintype "bidirectional"))
    )
    (net (code "31") (name "PB9") (class "Default")
      (node (ref "H2") (pin "10") (pinfunction "10_10") (pintype "unspecified"))
      (node (ref "U7") (pin "62") (pinfunction "PB9_62") (pintype "bidirectional"))
    )
    (net (code "32") (name "PB14") (class "Default")
      (node (ref "H3") (pin "11") (pinfunction "11_11") (pintype "unspecified"))
      (node (ref "U7") (pin "35") (pinfunction "PB14_35") (pintype "bidirectional"))
    )
    (net (code "33") (name "PB15") (class "Default")
      (node (ref "H3") (pin "10") (pinfunction "10_10") (pintype "unspecified"))
      (node (ref "U7") (pin "36") (pinfunction "PB15_36") (pintype "bidirectional"))
    )
    (net (code "34") (name "PC1") (class "Default")
      (node (ref "H1") (pin "1") (pinfunction "1_1") (pintype "unspecified"))
      (node (ref "U7") (pin "9") (pinfunction "PC1_9") (pintype "bidirectional"))
    )
    (net (code "35") (name "PC6") (class "Default")
      (node (ref "H3") (pin "9") (pinfunction "9_9") (pintype "unspecified"))
      (node (ref "U7") (pin "37") (pinfunction "PC6_37") (pintype "bidirectional"))
    )
    (net (code "36") (name "PC7") (class "Default")
      (node (ref "H3") (pin "8") (pinfunction "8_8") (pintype "unspecified"))
      (node (ref "U7") (pin "38") (pinfunction "PC7_38") (pintype "bidirectional"))
    )
    (net (code "37") (name "PC8") (class "Default")
      (node (ref "H3") (pin "7") (pinfunction "7_7") (pintype "unspecified"))
      (node (ref "U7") (pin "39") (pinfunction "PC8_39") (pintype "bidirectional"))
    )
    (net (code "38") (name "PC9") (class "Default")
      (node (ref "H3") (pin "6") (pinfunction "6_6") (pintype "unspecified"))
      (node (ref "U7") (pin "40") (pinfunction "PC9_40") (pintype "bidirectional"))
    )
    (net (code "39") (name "PC10") (class "Default")
      (node (ref "H2") (pin "1") (pinfunction "1_1") (pintype "unspecified"))
      (node (ref "U7") (pin "51") (pinfunction "PC10_51") (pintype "bidirectional"))
    )
    (net (code "40") (name "PC11") (class "Default")
      (node (ref "H2") (pin "2") (pinfunction "2_2") (pintype "unspecified"))
      (node (ref "U7") (pin "52") (pinfunction "PC11_52") (pintype "bidirectional"))
    )
    (net (code "41") (name "PC12") (class "Default")
      (node (ref "H2") (pin "3") (pinfunction "3_3") (pintype "unspecified"))
      (node (ref "U7") (pin "53") (pinfunction "PC12_53") (pintype "bidirectional"))
    )
    (net (code "42") (name "PD2") (class "Default")
      (node (ref "H2") (pin "4") (pinfunction "4_4") (pintype "unspecified"))
      (node (ref "U7") (pin "54") (pinfunction "PD2_54") (pintype "bidirectional"))
    )
    (net (code "43") (name "RESET") (class "Default")
      (node (ref "C10") (pin "1") (pinfunction "1_1") (pintype "input"))
      (node (ref "R11") (pin "2") (pinfunction "2_2") (pintype "input"))
      (node (ref "USB3301") (pin "9") (pinfunction "RESET_9") (pintype "unspecified"))
    )
    (net (code "44") (name "SWCLK") (class "Default")
      (node (ref "H4") (pin "1") (pinfunction "1_1") (pintype "unspecified"))
      (node (ref "U7") (pin "49") (pinfunction "PA14(JTCK-SWCLK)_49") (pintype "bidirectional"))
    )
    (net (code "45") (name "SWDIO") (class "Default")
      (node (ref "H4") (pin "2") (pinfunction "2_2") (pintype "unspecified"))
      (node (ref "U7") (pin "46") (pinfunction "PA13(JTMS-SWDIO)_46") (pintype "bidirectional"))
    )
    (net (code "46") (name "USB-CK") (class "Default")
      (node (ref "U7") (pin "21") (pinfunction "PA5_21") (pintype "bidirectional"))
      (node (ref "USB3301") (pin "14") (pinfunction "CLKOUT_14") (pintype "unspecified"))
    )
    (net (code "47") (name "USB-D0") (class "Default")
      (node (ref "U7") (pin "17") (pinfunction "PA3_17") (pintype "bidirectional"))
      (node (ref "USB3301") (pin "24") (pinfunction "DATA0_24") (pintype "unspecified"))
    )
    (net (code "48") (name "USB-D1") (class "Default")
      (node (ref "U7") (pin "26") (pinfunction "PB0_26") (pintype "bidirectional"))
      (node (ref "USB3301") (pin "23") (pinfunction "DATA1_23") (pintype "unspecified"))
    )
    (net (code "49") (name "USB-D2") (class "Default")
      (node (ref "U7") (pin "27") (pinfunction "PB1_27") (pintype "bidirectional"))
      (node (ref "USB3301") (pin "22") (pinfunction "DATA2_22") (pintype "unspecified"))
    )
    (net (code "50") (name "USB-D3") (class "Default")
      (node (ref "U7") (pin "29") (pinfunction "PB10_29") (pintype "bidirectional"))
      (node (ref "USB3301") (pin "21") (pinfunction "DATA3_21") (pintype "unspecified"))
    )
    (net (code "51") (name "USB-D4") (class "Default")
      (node (ref "U7") (pin "30") (pinfunction "PB11_30") (pintype "bidirectional"))
      (node (ref "USB3301") (pin "20") (pinfunction "DATA4_20") (pintype "unspecified"))
    )
    (net (code "52") (name "USB-D5") (class "Default")
      (node (ref "U7") (pin "33") (pinfunction "PB12_33") (pintype "bidirectional"))
      (node (ref "USB3301") (pin "19") (pinfunction "DATA5_19") (pintype "unspecified"))
    )
    (net (code "53") (name "USB-D6") (class "Default")
      (node (ref "U7") (pin "34") (pinfunction "PB13_34") (pintype "bidirectional"))
      (node (ref "USB3301") (pin "18") (pinfunction "DATA6_18") (pintype "unspecified"))
    )
    (net (code "54") (name "USB-D7") (class "Default")
      (node (ref "U7") (pin "57") (pinfunction "PB5_57") (pintype "bidirectional"))
      (node (ref "USB3301") (pin "17") (pinfunction "DATA7_17") (pintype "unspecified"))
    )
    (net (code "55") (name "USB-DIR") (class "Default")
      (node (ref "U7") (pin "10") (pinfunction "PC2_10") (pintype "bidirectional"))
      (node (ref "USB3301") (pin "12") (pinfunction "DIR_12") (pintype "unspecified"))
    )
    (net (code "56") (name "USB-NXT") (class "Default")
      (node (ref "U7") (pin "11") (pinfunction "PC3_11") (pintype "bidirectional"))
      (node (ref "USB3301") (pin "11") (pinfunction "NXT_11") (pintype "unspecified"))
    )
    (net (code "57") (name "USB-STP") (class "Default")
      (node (ref "U7") (pin "8") (pinfunction "PC0_8") (pintype "bidirectional"))
      (node (ref "USB3301") (pin "13") (pinfunction "STP_13") (pintype "unspecified"))
    )
    (net (code "58") (name "USBC1_CC1") (class "Default")
      (node (ref "R14") (pin "1") (pinfunction "1_1") (pintype "input"))
      (node (ref "USBC2") (pin "A5") (pinfunction "CC1_A5") (pintype "unspecified"))
    )
    (net (code "59") (name "USBC1_CC2") (class "Default")
      (node (ref "R15") (pin "1") (pinfunction "1_1") (pintype "input"))
      (node (ref "USBC2") (pin "B5") (pinfunction "CC2_B5") (pintype "unspecified"))
    )
    (net (code "60") (name "VCC+5V") (class "Default")
      (node (ref "C11") (pin "1") (pinfunction "1_1") (pintype "unspecified"))
      (node (ref "C12") (pin "2") (pinfunction "2_2") (pintype "unspecified"))
      (node (ref "R24") (pin "1") (pinfunction "1_1") (pintype "input"))
      (node (ref "U2") (pin "3") (pinfunction "VIN_3") (pintype "unspecified"))
      (node (ref "USBC2") (pin "A4") (pinfunction "VBUS_A4") (pintype "unspecified"))
      (node (ref "USBC2") (pin "A9") (pinfunction "VBUS_A9") (pintype "unspecified"))
      (node (ref "USBC2") (pin "B4") (pinfunction "VBUS_B4") (pintype "unspecified"))
      (node (ref "USBC2") (pin "B9") (pinfunction "VBUS_B9") (pintype "unspecified"))
    )
    (net (code "61") (name "VDD1.8") (class "Default")
      (node (ref "USB3301") (pin "15") (pinfunction "VDD1.8_15") (pintype "unspecified"))
      (node (ref "USB3301") (pin "26") (pinfunction "VDD1.8_26") (pintype "unspecified"))
      (node (ref "USB3301") (pin "29") (pinfunction "VDDA1.8_29") (pintype "unspecified"))
    )
    (net (code "62") (name "XI") (class "Default")
      (node (ref "C23") (pin "2") (pinfunction "2_2") (pintype "input"))
      (node (ref "R23") (pin "2") (pinfunction "2_2") (pintype "input"))
      (node (ref "USB3301") (pin "28") (pinfunction "XI_28") (pintype "unspecified"))
      (node (ref "X4") (pin "1") (pinfunction "OSC1_1") (pintype "input"))
    )
    (net (code "63") (name "XO") (class "Default")
      (node (ref "C24") (pin "2") (pinfunction "2_2") (pintype "input"))
      (node (ref "R23") (pin "1") (pinfunction "1_1") (pintype "input"))
      (node (ref "USB3301") (pin "27") (pinfunction "XO_27") (pintype "unspecified"))
      (node (ref "X4") (pin "2") (pinfunction "OSC2_2") (pintype "input"))
    )
    (net (code "64") (name "unconnected-(R14-Pad2)") (class "Default")
      (node (ref "R14") (pin "2") (pinfunction "2_2") (pintype "input"))
    )
    (net (code "65") (name "unconnected-(U7A-PC4-Pad24)") (class "Default")
      (node (ref "U7") (pin "24") (pinfunction "PC4_24") (pintype "bidirectional+no_connect"))
    )
    (net (code "66") (name "unconnected-(U7A-PC5-Pad25)") (class "Default")
      (node (ref "U7") (pin "25") (pinfunction "PC5_25") (pintype "bidirectional+no_connect"))
    )
    (net (code "67") (name "unconnected-(U7A-PC13-Pad2)") (class "Default")
      (node (ref "U7") (pin "2") (pinfunction "PC13_2") (pintype "bidirectional+no_connect"))
    )
    (net (code "68") (name "unconnected-(U7A-PC14-OSC32_IN(PC14)-Pad3)") (class "Default")
      (node (ref "U7") (pin "3") (pinfunction "PC14-OSC32_IN(PC14)_3") (pintype "bidirectional+no_connect"))
    )
    (net (code "69") (name "unconnected-(U7A-PC15-OSC32_OUT(PC15)-Pad4)") (class "Default")
      (node (ref "U7") (pin "4") (pinfunction "PC15-OSC32_OUT(PC15)_4") (pintype "bidirectional+no_connect"))
    )
    (net (code "70") (name "unconnected-(USB3301-CPEN-Pad3)") (class "Default")
      (node (ref "USB3301") (pin "3") (pinfunction "CPEN_3") (pintype "unspecified+no_connect"))
    )
    (net (code "71") (name "unconnected-(USB3301-EXTVBUS-Pad10)") (class "Default")
      (node (ref "USB3301") (pin "10") (pinfunction "EXTVBUS_10") (pintype "unspecified+no_connect"))
    )
    (net (code "72") (name "unconnected-(USB3301-GND-Pad1)") (class "Default")
      (node (ref "USB3301") (pin "1") (pinfunction "GND_1") (pintype "unspecified+no_connect"))
    )
    (net (code "73") (name "unconnected-(USB3301-GND-Pad2)") (class "Default")
      (node (ref "USB3301") (pin "2") (pinfunction "GND_2") (pintype "unspecified+no_connect"))
    )
    (net (code "74") (name "unconnected-(USB3301-ID-Pad5)") (class "Default")
      (node (ref "USB3301") (pin "5") (pinfunction "ID_5") (pintype "unspecified+no_connect"))
    )
    (net (code "75") (name "unconnected-(USBC2-SBU1-PadA8)") (class "Default")
      (node (ref "USBC2") (pin "A8") (pinfunction "SBU1_A8") (pintype "unspecified+no_connect"))
    )
    (net (code "76") (name "unconnected-(USBC2-SBU2-PadB8)") (class "Default")
      (node (ref "USBC2") (pin "B8") (pinfunction "SBU2_B8") (pintype "unspecified+no_connect"))
    )
  )
)
